# TinyPICO.net
KiCad netlist of a schematic drawn in EAGLE
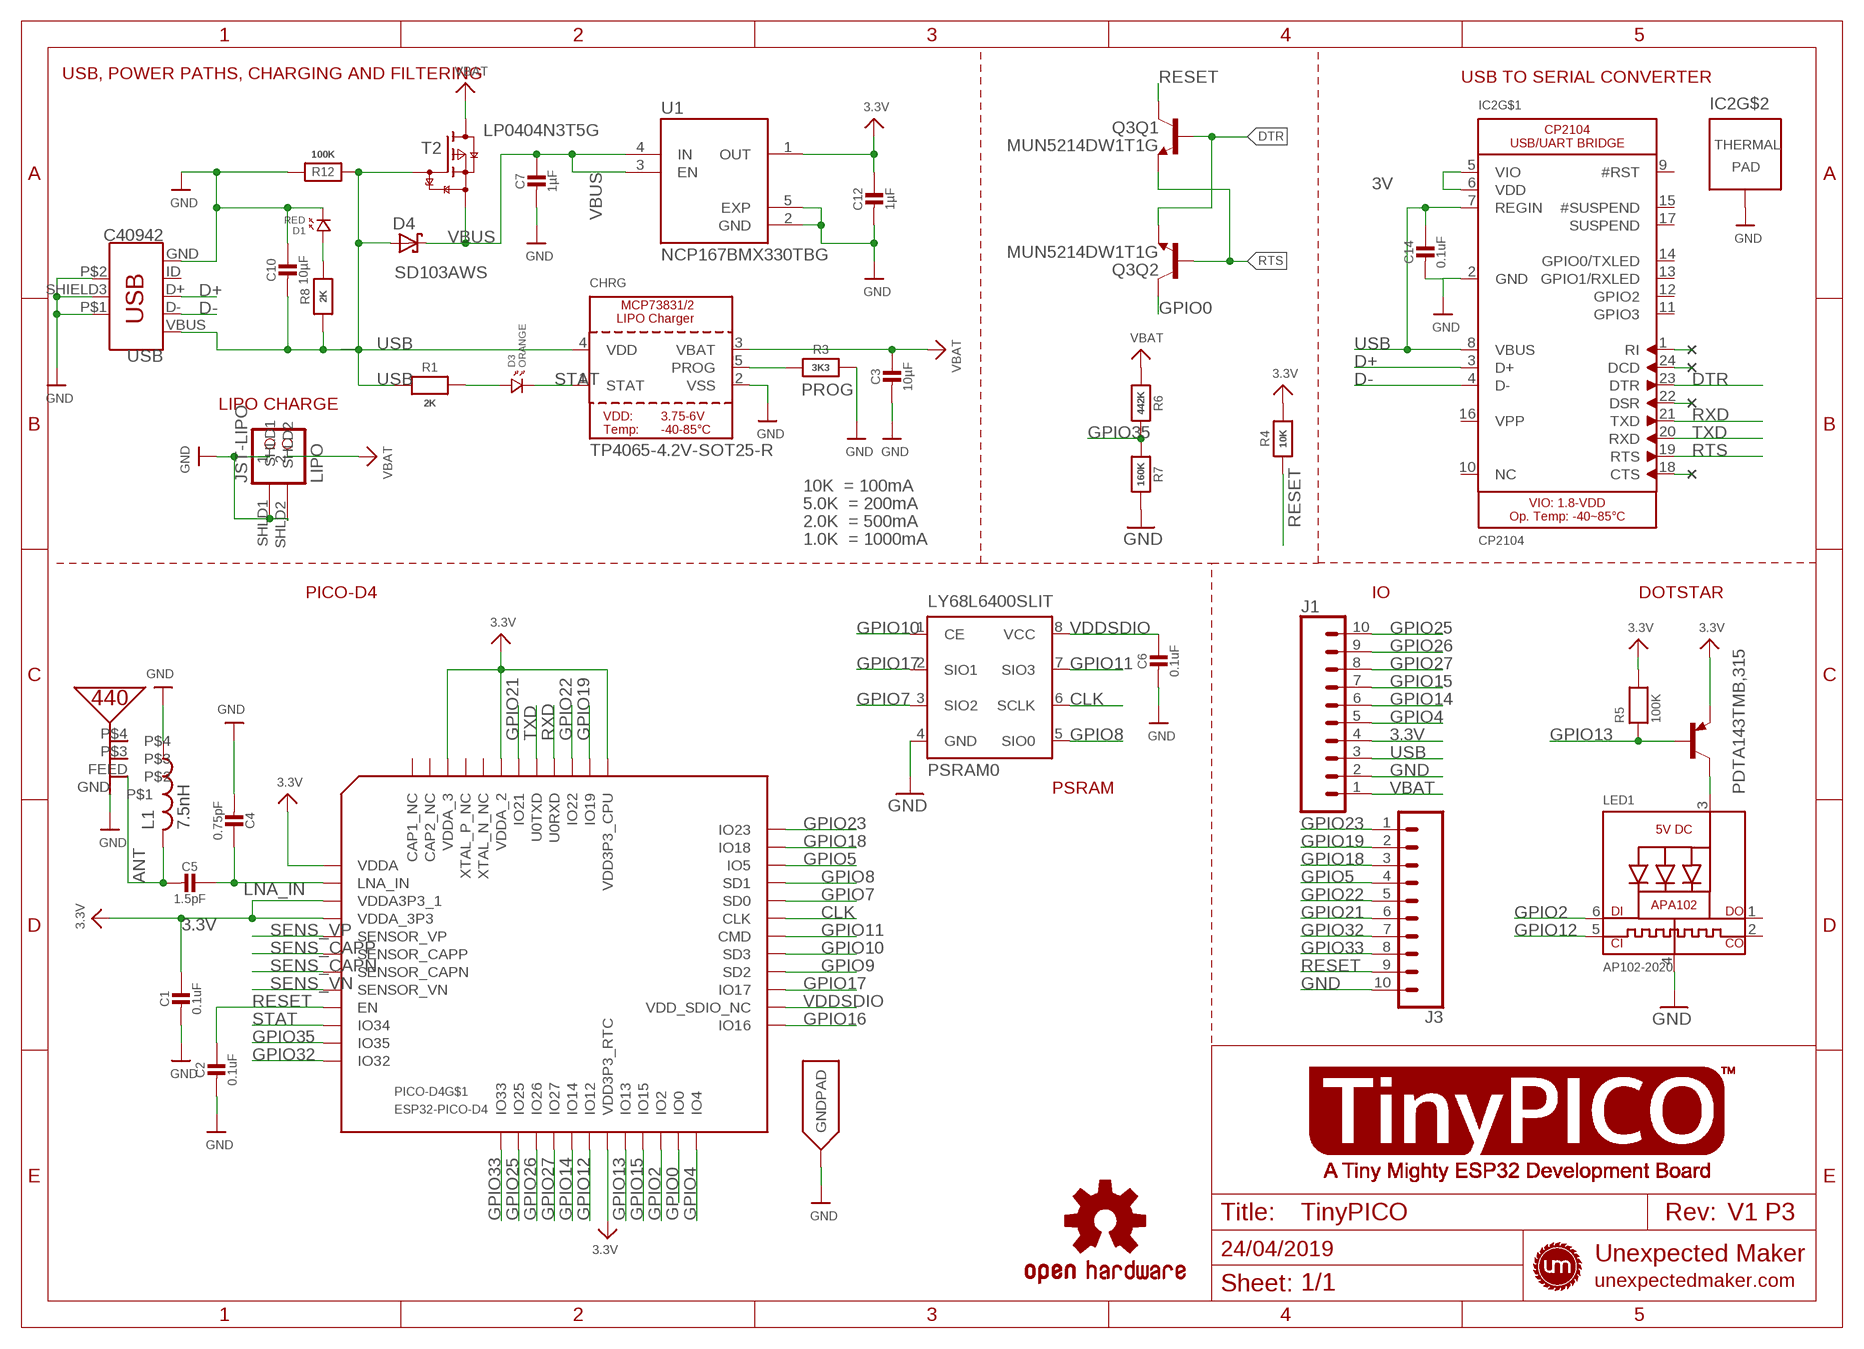
[diagram p0: schematic, sheet 1]

(export (version "E")
  (design (tool "Eeschema 10.0.6"))
  (components
    (comp (ref "C1")
      (value "0.1uF")
      (footprint "eagle-import:_0402MP")
      (libsource (lib "eagle-import") (part "CAP_CERAMIC_0402MP"))
    )
    (comp (ref "C2")
      (value "0.1uF")
      (footprint "eagle-import:_0402MP")
      (libsource (lib "eagle-import") (part "CAP_CERAMIC_0402MP"))
    )
    (comp (ref "C3")
      (value "10µF")
      (footprint "eagle-import:_0603MP")
      (libsource (lib "eagle-import") (part "CAP_CERAMIC_0603MP"))
    )
    (comp (ref "C4")
      (value "0.75pF")
      (footprint "eagle-import:_0402MP")
      (libsource (lib "eagle-import") (part "CAP_CERAMIC_0402MP"))
    )
    (comp (ref "C5")
      (value "1.5pF")
      (footprint "eagle-import:_0402MP")
      (libsource (lib "eagle-import") (part "CAP_CERAMIC_0402MP"))
    )
    (comp (ref "C6")
      (value "0.1uF")
      (footprint "eagle-import:_0402MP")
      (libsource (lib "eagle-import") (part "CAP_CERAMIC_0402MP"))
    )
    (comp (ref "C7")
      (value "1µF")
      (footprint "eagle-import:_0402MP")
      (libsource (lib "eagle-import") (part "CAP_CERAMIC_0402MP"))
    )
    (comp (ref "C10")
      (value "10µF")
      (footprint "eagle-import:_0603MP")
      (libsource (lib "eagle-import") (part "CAP_CERAMIC_0603MP"))
    )
    (comp (ref "C12")
      (value "1µF")
      (footprint "eagle-import:_0402MP")
      (libsource (lib "eagle-import") (part "CAP_CERAMIC_0402MP"))
    )
    (comp (ref "C14")
      (value "0.1uF")
      (footprint "eagle-import:_0402MP")
      (libsource (lib "eagle-import") (part "CAP_CERAMIC_0402MP"))
    )
    (comp (ref "CHRG")
      (value "TP4065-4.2V-SOT25-R")
      (footprint "eagle-import:SOT23-5")
      (libsource (lib "eagle-import") (part "MCP73831/2"))
    )
    (comp (ref "D1")
      (value "RED")
      (footprint "eagle-import:0402.LED")
      (libsource (lib "eagle-import") (part "LED.0402"))
    )
    (comp (ref "D3")
      (value "ORANGE")
      (footprint "eagle-import:0402.LED")
      (libsource (lib "eagle-import") (part "LED.0402"))
    )
    (comp (ref "D4")
      (value "BAT60J")
      (footprint "eagle-import:SOD323_ST")
      (libsource (lib "eagle-import") (part "BAT60J"))
    )
    (comp (ref "IC2")
      (value "CP2104")
      (footprint "eagle-import:MICROBUILDER_QFN24_4MM_SMSC")
      (libsource (lib "eagle-import") (part "MICROBUILDER_CP2104"))
    )
    (comp (ref "J1")
      (value "TINYPICO_HEADER_10NO_SILK_PTH_FEMALE")
      (footprint "eagle-import:1X10_NO_SILK")
      (libsource (lib "eagle-import") (part "TINYPICO_HEADER_10NO_SILK_PTH_FEMALE"))
    )
    (comp (ref "J3")
      (value "TINYPICO_HEADER_10NO_SILK_PTH_FEMALE")
      (footprint "eagle-import:1X10_NO_SILK")
      (libsource (lib "eagle-import") (part "TINYPICO_HEADER_10NO_SILK_PTH_FEMALE"))
    )
    (comp (ref "JST-LIPO")
      (value "LIPO")
      (footprint "eagle-import:JSTPH2")
      (libsource (lib "eagle-import") (part "JST_2PIN"))
    )
    (comp (ref "L1")
      (value "7.5nH")
      (footprint "eagle-import:RESC0402_N")
      (libsource (lib "eagle-import") (part "INDUCTOR_0402_N"))
    )
    (comp (ref "LED1")
      (value "AP102-2020")
      (footprint "eagle-import:MICROBUILDER_APA102_2020")
      (libsource (lib "eagle-import") (part "MICROBUILDER_APA1022020"))
    )
    (comp (ref "LOGO1")
      (value "OSHW-LOGOS")
      (footprint "eagle-import:OSHW-LOGO-S")
      (libsource (lib "eagle-import") (part "OSHW-LOGOS"))
    )
    (comp (ref "LY68L6400SLIT")
      (value "PSRAM0")
      (footprint "eagle-import:SOP8")
      (fields (field (name "MPN") "BD6230F-E2"))
      (libsource (lib "eagle-import") (part "PSRAM0"))
    )
    (comp (ref "PDTA143TMB,315")
      (value "TINYPICO-PNPAMB")
      (footprint "eagle-import:SOT883(B)")
      (libsource (lib "eagle-import") (part "TINYPICO-PNPMBA"))
    )
    (comp (ref "PICO-D4")
      (value "ESP32-PICO-D4")
      (footprint "eagle-import:PICO-D4-QFN48")
      (libsource (lib "eagle-import") (part "ESP32-PICO-D4"))
    )
    (comp (ref "Q3")
      (value "MUN5214DW1T1G")
      (footprint "eagle-import:DUAL_NPN_SC70-6")
      (libsource (lib "eagle-import") (part "MBT3904DW1T1"))
    )
    (comp (ref "R1")
      (value "2K")
      (footprint "eagle-import:_0402MP")
      (libsource (lib "eagle-import") (part "RESISTOR_0402MP"))
    )
    (comp (ref "R3")
      (value "3K3")
      (footprint "eagle-import:_0402MP")
      (libsource (lib "eagle-import") (part "RESISTOR_0402MP"))
    )
    (comp (ref "R4")
      (value "10K")
      (footprint "eagle-import:_0402MP")
      (libsource (lib "eagle-import") (part "RESISTOR_0402MP"))
    )
    (comp (ref "R5")
      (value "100K")
      (footprint "eagle-import:_0402MP")
      (libsource (lib "eagle-import") (part "RESISTOR_0402MP"))
    )
    (comp (ref "R6")
      (value "442K")
      (footprint "eagle-import:_0402MP")
      (libsource (lib "eagle-import") (part "RESISTOR_0402MP"))
    )
    (comp (ref "R7")
      (value "160K")
      (footprint "eagle-import:_0402MP")
      (libsource (lib "eagle-import") (part "RESISTOR_0402MP"))
    )
    (comp (ref "R8")
      (value "2K")
      (footprint "eagle-import:_0402MP")
      (libsource (lib "eagle-import") (part "RESISTOR_0402MP"))
    )
    (comp (ref "R12")
      (value "100K")
      (footprint "eagle-import:_0402MP")
      (libsource (lib "eagle-import") (part "RESISTOR_0402MP"))
    )
    (comp (ref "T2")
      (value "TINYPICO-P-FETKMB")
      (footprint "eagle-import:SOT883(B)")
      (libsource (lib "eagle-import") (part "TINYPICO-P-FETMBK"))
    )
    (comp (ref "U$8")
      (value "PRO-OB-440")
      (footprint "eagle-import:PRO-OB-440")
      (libsource (lib "eagle-import") (part "PRO-OB-440"))
    )
    (comp (ref "U1")
      (value "NCP170AMX300TCG")
      (footprint "eagle-import:VREG_NCP170AMX300TCG")
      (fields (field (name "MF") "ON Semiconductor"))
      (libsource (lib "eagle-import") (part "NCP170AMX300TCG"))
    )
    (comp (ref "USB")
      (value "C40942")
      (footprint "eagle-import:USB-B-MICRO-SMD")
      (libsource (lib "eagle-import") (part "TINYPICO_USB_FEMALE-SMT"))
    )
  )
  (nets
    (net (code "1") (name "/3V") (class "Default")
      (node (ref "IC2") (pin "5") (pinfunction "VIO_5") (pintype "power_in"))
      (node (ref "IC2") (pin "6") (pinfunction "VDD_6") (pintype "power_in"))
    )
    (net (code "2") (name "/ANT") (class "Default")
      (node (ref "C5") (pin "2") (pinfunction "2_2") (pintype "passive"))
      (node (ref "L1") (pin "2") (pinfunction "2_2") (pintype "passive"))
      (node (ref "U$8") (pin "FEED") (pinfunction "P$2_FEED") (pintype "input"))
    )
    (net (code "3") (name "/CLK") (class "Default")
      (node (ref "LY68L6400SLIT") (pin "6") (pinfunction "SCLK_6") (pintype "passive"))
      (node (ref "PICO-D4") (pin "31") (pinfunction "CLK_31") (pintype "bidirectional"))
    )
    (net (code "4") (name "/D+") (class "Default")
      (node (ref "IC2") (pin "3") (pinfunction "D+_3") (pintype "bidirectional"))
      (node (ref "USB") (pin "D+") (pinfunction "D+_D+") (pintype "bidirectional"))
    )
    (net (code "5") (name "/D-") (class "Default")
      (node (ref "IC2") (pin "4") (pinfunction "D-_4") (pintype "bidirectional"))
      (node (ref "USB") (pin "D-") (pinfunction "D-_D-") (pintype "bidirectional"))
    )
    (net (code "6") (name "/GPIO0") (class "Default")
      (node (ref "PICO-D4") (pin "23") (pinfunction "IO0_23") (pintype "bidirectional"))
      (node (ref "Q3") (pin "6") (pinfunction "C_6") (pintype "passive"))
    )
    (net (code "7") (name "/GPIO2") (class "Default")
      (node (ref "LED1") (pin "6") (pinfunction "DI_6") (pintype "input"))
      (node (ref "PICO-D4") (pin "22") (pinfunction "IO2_22") (pintype "bidirectional"))
    )
    (net (code "8") (name "/GPIO4") (class "Default")
      (node (ref "J1") (pin "5") (pinfunction "5_5") (pintype "passive"))
      (node (ref "PICO-D4") (pin "24") (pinfunction "IO4_24") (pintype "bidirectional"))
    )
    (net (code "9") (name "/GPIO5") (class "Default")
      (node (ref "J3") (pin "4") (pinfunction "4_4") (pintype "passive"))
      (node (ref "PICO-D4") (pin "34") (pinfunction "IO5_34") (pintype "bidirectional"))
    )
    (net (code "10") (name "/GPIO7") (class "Default")
      (node (ref "LY68L6400SLIT") (pin "3") (pinfunction "SIO2_3") (pintype "power_in"))
      (node (ref "PICO-D4") (pin "32") (pinfunction "SD0_32") (pintype "bidirectional"))
    )
    (net (code "11") (name "/GPIO8") (class "Default")
      (node (ref "LY68L6400SLIT") (pin "5") (pinfunction "SIO0_5") (pintype "input"))
      (node (ref "PICO-D4") (pin "33") (pinfunction "SD1_33") (pintype "bidirectional"))
    )
    (net (code "12") (name "/GPIO9") (class "Default")
      (node (ref "PICO-D4") (pin "28") (pinfunction "SD2_28") (pintype "bidirectional"))
    )
    (net (code "13") (name "/GPIO10") (class "Default")
      (node (ref "LY68L6400SLIT") (pin "1") (pinfunction "CE_1") (pintype "output"))
      (node (ref "PICO-D4") (pin "29") (pinfunction "SD3_29") (pintype "bidirectional"))
    )
    (net (code "14") (name "/GPIO11") (class "Default")
      (node (ref "LY68L6400SLIT") (pin "7") (pinfunction "SIO3_7") (pintype "output"))
      (node (ref "PICO-D4") (pin "30") (pinfunction "CMD_30") (pintype "bidirectional"))
    )
    (net (code "15") (name "/GPIO12") (class "Default")
      (node (ref "LED1") (pin "5") (pinfunction "CKI_5") (pintype "input"))
      (node (ref "PICO-D4") (pin "18") (pinfunction "IO12_18") (pintype "power_in"))
    )
    (net (code "16") (name "/GPIO13") (class "Default")
      (node (ref "PDTA143TMB,315") (pin "1") (pinfunction "B_1") (pintype "passive"))
      (node (ref "PICO-D4") (pin "20") (pinfunction "IO13_20") (pintype "bidirectional"))
      (node (ref "R5") (pin "1") (pinfunction "1_1") (pintype "passive"))
    )
    (net (code "17") (name "/GPIO14") (class "Default")
      (node (ref "J1") (pin "6") (pinfunction "6_6") (pintype "passive"))
      (node (ref "PICO-D4") (pin "17") (pinfunction "IO14_17") (pintype "bidirectional"))
    )
    (net (code "18") (name "/GPIO15") (class "Default")
      (node (ref "J1") (pin "7") (pinfunction "7_7") (pintype "passive"))
      (node (ref "PICO-D4") (pin "21") (pinfunction "IO15_21") (pintype "bidirectional"))
    )
    (net (code "19") (name "/GPIO16") (class "Default")
      (node (ref "PICO-D4") (pin "25") (pinfunction "IO16_25") (pintype "bidirectional"))
    )
    (net (code "20") (name "/GPIO17") (class "Default")
      (node (ref "LY68L6400SLIT") (pin "2") (pinfunction "SIO1_2") (pintype "power_in"))
      (node (ref "PICO-D4") (pin "27") (pinfunction "IO17_27") (pintype "bidirectional"))
    )
    (net (code "21") (name "/GPIO18") (class "Default")
      (node (ref "J3") (pin "3") (pinfunction "3_3") (pintype "passive"))
      (node (ref "PICO-D4") (pin "35") (pinfunction "IO18_35") (pintype "bidirectional"))
    )
    (net (code "22") (name "/GPIO19") (class "Default")
      (node (ref "J3") (pin "2") (pinfunction "2_2") (pintype "passive"))
      (node (ref "PICO-D4") (pin "38") (pinfunction "IO19_38") (pintype "bidirectional"))
    )
    (net (code "23") (name "/GPIO21") (class "Default")
      (node (ref "J3") (pin "6") (pinfunction "6_6") (pintype "passive"))
      (node (ref "PICO-D4") (pin "42") (pinfunction "IO21_42") (pintype "power_in"))
    )
    (net (code "24") (name "/GPIO22") (class "Default")
      (node (ref "J3") (pin "5") (pinfunction "5_5") (pintype "passive"))
      (node (ref "PICO-D4") (pin "39") (pinfunction "IO22_39") (pintype "bidirectional"))
    )
    (net (code "25") (name "/GPIO23") (class "Default")
      (node (ref "J3") (pin "1") (pinfunction "1_1") (pintype "passive"))
      (node (ref "PICO-D4") (pin "36") (pinfunction "IO23_36") (pintype "bidirectional"))
    )
    (net (code "26") (name "/GPIO25") (class "Default")
      (node (ref "J1") (pin "10") (pinfunction "10_10") (pintype "passive"))
      (node (ref "PICO-D4") (pin "14") (pinfunction "IO25_14") (pintype "bidirectional"))
    )
    (net (code "27") (name "/GPIO26") (class "Default")
      (node (ref "J1") (pin "9") (pinfunction "9_9") (pintype "passive"))
      (node (ref "PICO-D4") (pin "15") (pinfunction "IO26_15") (pintype "bidirectional"))
    )
    (net (code "28") (name "/GPIO27") (class "Default")
      (node (ref "J1") (pin "8") (pinfunction "8_8") (pintype "passive"))
      (node (ref "PICO-D4") (pin "16") (pinfunction "IO27_16") (pintype "bidirectional"))
    )
    (net (code "29") (name "/GPIO32") (class "Default")
      (node (ref "J3") (pin "7") (pinfunction "7_7") (pintype "passive"))
      (node (ref "PICO-D4") (pin "12") (pinfunction "IO32_12") (pintype "bidirectional"))
    )
    (net (code "30") (name "/GPIO33") (class "Default")
      (node (ref "J3") (pin "8") (pinfunction "8_8") (pintype "passive"))
      (node (ref "PICO-D4") (pin "13") (pinfunction "IO33_13") (pintype "bidirectional"))
    )
    (net (code "31") (name "/GPIO35") (class "Default")
      (node (ref "PICO-D4") (pin "11") (pinfunction "IO35_11") (pintype "bidirectional"))
      (node (ref "R6") (pin "2") (pinfunction "2_2") (pintype "passive"))
      (node (ref "R7") (pin "1") (pinfunction "1_1") (pintype "passive"))
    )
    (net (code "32") (name "/LNA_IN") (class "Default")
      (node (ref "C4") (pin "1") (pinfunction "1_1") (pintype "passive"))
      (node (ref "C5") (pin "1") (pinfunction "1_1") (pintype "passive"))
      (node (ref "PICO-D4") (pin "2") (pinfunction "LNA_IN_2") (pintype "bidirectional"))
    )
    (net (code "33") (name "/PROG") (class "Default")
      (node (ref "CHRG") (pin "5") (pinfunction "PROG_5") (pintype "input"))
      (node (ref "R3") (pin "1") (pinfunction "1_1") (pintype "passive"))
    )
    (net (code "34") (name "/RESET") (class "Default")
      (node (ref "C2") (pin "1") (pinfunction "1_1") (pintype "passive"))
      (node (ref "J3") (pin "9") (pinfunction "9_9") (pintype "passive"))
      (node (ref "PICO-D4") (pin "9") (pinfunction "EN_9") (pintype "bidirectional"))
      (node (ref "Q3") (pin "3") (pinfunction "C_3") (pintype "passive"))
      (node (ref "R4") (pin "1") (pinfunction "1_1") (pintype "passive"))
    )
    (net (code "35") (name "/RXD") (class "Default")
      (node (ref "IC2") (pin "21") (pinfunction "TXD_21") (pintype "output"))
      (node (ref "PICO-D4") (pin "40") (pinfunction "U0RXD_40") (pintype "bidirectional"))
    )
    (net (code "36") (name "/SENS_CAPN") (class "Default")
      (node (ref "PICO-D4") (pin "7") (pinfunction "SENSOR_CAPN_7") (pintype "power_in"))
    )
    (net (code "37") (name "/SENS_CAPP") (class "Default")
      (node (ref "PICO-D4") (pin "6") (pinfunction "SENSOR_CAPP_6") (pintype "bidirectional"))
    )
    (net (code "38") (name "/SENS_VN") (class "Default")
      (node (ref "PICO-D4") (pin "8") (pinfunction "SENSOR_VN_8") (pintype "bidirectional"))
    )
    (net (code "39") (name "/SENS_VP") (class "Default")
      (node (ref "PICO-D4") (pin "5") (pinfunction "SENSOR_VP_5") (pintype "bidirectional"))
    )
    (net (code "40") (name "/STAT") (class "Default")
      (node (ref "CHRG") (pin "1") (pinfunction "STAT_1") (pintype "output"))
      (node (ref "D3") (pin "P$2") (pinfunction "2_P$2") (pintype "bidirectional"))
      (node (ref "PICO-D4") (pin "10") (pinfunction "IO34_10") (pintype "bidirectional"))
    )
    (net (code "41") (name "/TXD") (class "Default")
      (node (ref "IC2") (pin "20") (pinfunction "RXD_20") (pintype "input"))
      (node (ref "PICO-D4") (pin "41") (pinfunction "U0TXD_41") (pintype "bidirectional"))
    )
    (net (code "42") (name "/USB") (class "Default")
      (node (ref "C10") (pin "2") (pinfunction "2_2") (pintype "passive"))
      (node (ref "C14") (pin "1") (pinfunction "1_1") (pintype "passive"))
      (node (ref "CHRG") (pin "4") (pinfunction "VDD_4") (pintype "power_in"))
      (node (ref "D4") (pin "A") (pinfunction "A_A") (pintype "passive"))
      (node (ref "IC2") (pin "7") (pinfunction "REGIN_7") (pintype "power_in"))
      (node (ref "IC2") (pin "8") (pinfunction "VBUS_8") (pintype "power_in"))
      (node (ref "J1") (pin "3") (pinfunction "3_3") (pintype "passive"))
      (node (ref "R1") (pin "1") (pinfunction "1_1") (pintype "passive"))
      (node (ref "R12") (pin "1") (pinfunction "1_1") (pintype "passive"))
      (node (ref "R8") (pin "1") (pinfunction "1_1") (pintype "passive"))
      (node (ref "T2") (pin "1") (pinfunction "G_1") (pintype "passive"))
      (node (ref "USB") (pin "VBUS") (pinfunction "VBUS_VBUS") (pintype "power_in"))
    )
    (net (code "43") (name "/VBUS") (class "Default")
      (node (ref "C7") (pin "1") (pinfunction "1_1") (pintype "passive"))
      (node (ref "D4") (pin "C") (pinfunction "C_C") (pintype "passive"))
      (node (ref "T2") (pin "2") (pinfunction "S_2") (pintype "passive"))
      (node (ref "U1") (pin "3") (pinfunction "EN_3") (pintype "input"))
      (node (ref "U1") (pin "4") (pinfunction "IN_4") (pintype "input"))
    )
    (net (code "44") (name "/VDDSDIO") (class "Default")
      (node (ref "C6") (pin "1") (pinfunction "1_1") (pintype "passive"))
      (node (ref "LY68L6400SLIT") (pin "8") (pinfunction "VCC_8") (pintype "power_in"))
      (node (ref "PICO-D4") (pin "26") (pinfunction "VDD_SDIO_NC_26") (pintype "bidirectional"))
    )
    (net (code "45") (name "3.3V") (class "Default")
      (node (ref "C1") (pin "1") (pinfunction "1_1") (pintype "passive"))
      (node (ref "C12") (pin "1") (pinfunction "1_1") (pintype "passive"))
      (node (ref "J1") (pin "4") (pinfunction "4_4") (pintype "passive"))
      (node (ref "PDTA143TMB,315") (pin "2") (pinfunction "E_2") (pintype "passive"))
      (node (ref "PICO-D4") (pin "1") (pinfunction "VDDA_1") (pintype "bidirectional"))
      (node (ref "PICO-D4") (pin "19") (pinfunction "VDD3P3_RTC_19") (pintype "bidirectional"))
      (node (ref "PICO-D4") (pin "3") (pinfunction "VDDA3P3_1_3") (pintype "bidirectional"))
      (node (ref "PICO-D4") (pin "37") (pinfunction "VDD3P3_CPU_37") (pintype "bidirectional"))
      (node (ref "PICO-D4") (pin "4") (pinfunction "VDDA_3P3_4") (pintype "bidirectional"))
      (node (ref "PICO-D4") (pin "43") (pinfunction "VDDA_2_43") (pintype "bidirectional"))
      (node (ref "PICO-D4") (pin "46") (pinfunction "VDDA_3_46") (pintype "bidirectional"))
      (node (ref "R4") (pin "2") (pinfunction "2_2") (pintype "passive"))
      (node (ref "R5") (pin "2") (pinfunction "2_2") (pintype "passive"))
      (node (ref "U1") (pin "1") (pinfunction "OUT_1") (pintype "output"))
    )
    (net (code "46") (name "DTR") (class "Default")
      (node (ref "IC2") (pin "23") (pinfunction "DTR_23") (pintype "output"))
      (node (ref "Q3") (pin "1") (pinfunction "E_1") (pintype "passive"))
      (node (ref "Q3") (pin "5") (pinfunction "B_5") (pintype "passive"))
    )
    (net (code "47") (name "GND") (class "Default")
      (node (ref "C1") (pin "2") (pinfunction "2_2") (pintype "passive"))
      (node (ref "C10") (pin "1") (pinfunction "1_1") (pintype "passive"))
      (node (ref "C12") (pin "2") (pinfunction "2_2") (pintype "passive"))
      (node (ref "C14") (pin "2") (pinfunction "2_2") (pintype "passive"))
      (node (ref "C2") (pin "2") (pinfunction "2_2") (pintype "passive"))
      (node (ref "C3") (pin "2") (pinfunction "2_2") (pintype "passive"))
      (node (ref "C4") (pin "2") (pinfunction "2_2") (pintype "passive"))
      (node (ref "C6") (pin "2") (pinfunction "2_2") (pintype "passive"))
      (node (ref "C7") (pin "2") (pinfunction "2_2") (pintype "passive"))
      (node (ref "CHRG") (pin "2") (pinfunction "VSS_2") (pintype "power_in"))
      (node (ref "D1") (pin "P$2") (pinfunction "2_P$2") (pintype "bidirectional"))
      (node (ref "IC2") (pin "2") (pinfunction "GND_2") (pintype "power_in"))
      (node (ref "IC2") (pin "THERM") (pinfunction "TP_THERM") (pintype "power_in"))
      (node (ref "J1") (pin "2") (pinfunction "2_2") (pintype "passive"))
      (node (ref "J3") (pin "10") (pinfunction "10_10") (pintype "passive"))
      (node (ref "JST-LIPO") (pin "1") (pinfunction "1_1") (pintype "passive"))
      (node (ref "JST-LIPO") (pin "SHLD1") (pinfunction "SHLD1_SHLD1") (pintype "bidirectional"))
      (node (ref "JST-LIPO") (pin "SHLD2") (pinfunction "SHLD2_SHLD2") (pintype "bidirectional"))
      (node (ref "L1") (pin "1") (pinfunction "1_1") (pintype "passive"))
      (node (ref "LED1") (pin "4") (pinfunction "GND_4") (pintype "power_in"))
      (node (ref "LY68L6400SLIT") (pin "4") (pinfunction "GND_4") (pintype "input"))
      (node (ref "PICO-D4") (pin "EXP") (pinfunction "GNDPAD_EXP") (pintype "power_in"))
      (node (ref "R12") (pin "2") (pinfunction "2_2") (pintype "passive"))
      (node (ref "R3") (pin "2") (pinfunction "2_2") (pintype "passive"))
      (node (ref "R7") (pin "2") (pinfunction "2_2") (pintype "passive"))
      (node (ref "U$8") (pin "GND") (pinfunction "P$1_GND") (pintype "input"))
      (node (ref "U1") (pin "2") (pinfunction "GND_2") (pintype "power_in"))
      (node (ref "U1") (pin "5") (pinfunction "EXP_5") (pintype "power_in"))
      (node (ref "USB") (pin "GND") (pinfunction "GND_GND") (pintype "power_in"))
      (node (ref "USB") (pin "P$1") (pinfunction "SHIELD1_P$1") (pintype "bidirectional"))
      (node (ref "USB") (pin "P$2") (pinfunction "SHIELD2_P$2") (pintype "bidirectional"))
      (node (ref "USB") (pin "SHIELD3") (pinfunction "SHIELD_SHIELD3") (pintype "bidirectional"))
    )
    (net (code "48") (name "Net-(D1-1)") (class "Default")
      (node (ref "D1") (pin "P$1") (pinfunction "1_P$1") (pintype "bidirectional"))
      (node (ref "R8") (pin "2") (pinfunction "2_2") (pintype "passive"))
    )
    (net (code "49") (name "Net-(D3-1)") (class "Default")
      (node (ref "D3") (pin "P$1") (pinfunction "1_P$1") (pintype "bidirectional"))
      (node (ref "R1") (pin "2") (pinfunction "2_2") (pintype "passive"))
    )
    (net (code "50") (name "Net-(LED1-VDD)") (class "Default")
      (node (ref "LED1") (pin "3") (pinfunction "VDD_3") (pintype "power_in"))
      (node (ref "PDTA143TMB,315") (pin "3") (pinfunction "C_3") (pintype "passive"))
    )
    (net (code "51") (name "RTS") (class "Default")
      (node (ref "IC2") (pin "19") (pinfunction "RTS_19") (pintype "output"))
      (node (ref "Q3") (pin "2") (pinfunction "B_2") (pintype "passive"))
      (node (ref "Q3") (pin "4") (pinfunction "E_4") (pintype "passive"))
    )
    (net (code "52") (name "VBAT") (class "Default")
      (node (ref "C3") (pin "1") (pinfunction "1_1") (pintype "passive"))
      (node (ref "CHRG") (pin "3") (pinfunction "VBAT_3") (pintype "power_in"))
      (node (ref "J1") (pin "1") (pinfunction "1_1") (pintype "passive"))
      (node (ref "JST-LIPO") (pin "2") (pinfunction "2_2") (pintype "passive"))
      (node (ref "R6") (pin "1") (pinfunction "1_1") (pintype "passive"))
      (node (ref "T2") (pin "3") (pinfunction "D_3") (pintype "passive"))
    )
    (net (code "53") (name "unconnected-(IC2A-#RST-Pad9)") (class "Default")
      (node (ref "IC2") (pin "9") (pinfunction "#RST_9") (pintype "bidirectional"))
    )
    (net (code "54") (name "unconnected-(IC2A-#SUSPEND-Pad15)") (class "Default")
      (node (ref "IC2") (pin "15") (pinfunction "#SUSPEND_15") (pintype "output"))
    )
    (net (code "55") (name "unconnected-(IC2A-CTS-Pad18)") (class "Default")
      (node (ref "IC2") (pin "18") (pinfunction "CTS_18") (pintype "input"))
    )
    (net (code "56") (name "unconnected-(IC2A-DCD-Pad24)") (class "Default")
      (node (ref "IC2") (pin "24") (pinfunction "DCD_24") (pintype "input"))
    )
    (net (code "57") (name "unconnected-(IC2A-DSR-Pad22)") (class "Default")
      (node (ref "IC2") (pin "22") (pinfunction "DSR_22") (pintype "input"))
    )
    (net (code "58") (name "unconnected-(IC2A-GPIO0{slash}TXLED-Pad14)") (class "Default")
      (node (ref "IC2") (pin "14") (pinfunction "GPIO0/TXLED_14") (pintype "bidirectional"))
    )
    (net (code "59") (name "unconnected-(IC2A-GPIO1{slash}RXLED-Pad13)") (class "Default")
      (node (ref "IC2") (pin "13") (pinfunction "GPIO1/RXLED_13") (pintype "bidirectional"))
    )
    (net (code "60") (name "unconnected-(IC2A-GPIO2-Pad12)") (class "Default")
      (node (ref "IC2") (pin "12") (pinfunction "GPIO2_12") (pintype "bidirectional"))
    )
    (net (code "61") (name "unconnected-(IC2A-GPIO3-Pad11)") (class "Default")
      (node (ref "IC2") (pin "11") (pinfunction "GPIO3_11") (pintype "bidirectional"))
    )
    (net (code "62") (name "unconnected-(IC2A-NC-Pad10)") (class "Default")
      (node (ref "IC2") (pin "10") (pinfunction "NC_10") (pintype "no_connect"))
    )
    (net (code "63") (name "unconnected-(IC2A-RI-Pad1)") (class "Default")
      (node (ref "IC2") (pin "1") (pinfunction "RI_1") (pintype "input"))
    )
    (net (code "64") (name "unconnected-(IC2A-SUSPEND-Pad17)") (class "Default")
      (node (ref "IC2") (pin "17") (pinfunction "SUSPEND_17") (pintype "output"))
    )
    (net (code "65") (name "unconnected-(IC2A-VPP-Pad16)") (class "Default")
      (node (ref "IC2") (pin "16") (pinfunction "VPP_16") (pintype "bidirectional"))
    )
    (net (code "66") (name "unconnected-(LED1-CKO-Pad2)") (class "Default")
      (node (ref "LED1") (pin "2") (pinfunction "CKO_2") (pintype "output"))
    )
    (net (code "67") (name "unconnected-(LED1-DO-Pad1)") (class "Default")
      (node (ref "LED1") (pin "1") (pinfunction "DO_1") (pintype "output"))
    )
    (net (code "68") (name "unconnected-(PICO-D4A-CAP1_NC-Pad48)") (class "Default")
      (node (ref "PICO-D4") (pin "48") (pinfunction "CAP1_NC_48") (pintype "bidirectional"))
    )
    (net (code "69") (name "unconnected-(PICO-D4A-CAP2_NC-Pad47)") (class "Default")
      (node (ref "PICO-D4") (pin "47") (pinfunction "CAP2_NC_47") (pintype "bidirectional"))
    )
    (net (code "70") (name "unconnected-(PICO-D4A-XTAL_N_NC-Pad44)") (class "Default")
      (node (ref "PICO-D4") (pin "44") (pinfunction "XTAL_N_NC_44") (pintype "bidirectional"))
    )
    (net (code "71") (name "unconnected-(PICO-D4A-XTAL_P_NC-Pad45)") (class "Default")
      (node (ref "PICO-D4") (pin "45") (pinfunction "XTAL_P_NC_45") (pintype "bidirectional"))
    )
    (net (code "72") (name "unconnected-(U$8-PadP$3)") (class "Default")
      (node (ref "U$8") (pin "P$3") (pinfunction "P$3_P$3") (pintype "no_connect"))
    )
    (net (code "73") (name "unconnected-(U$8-PadP$4)") (class "Default")
      (node (ref "U$8") (pin "P$4") (pinfunction "P$4_P$4") (pintype "no_connect"))
    )
    (net (code "74") (name "unconnected-(USB-PadID)") (class "Default")
      (node (ref "USB") (pin "ID") (pinfunction "ID_ID") (pintype "bidirectional"))
    )
  )
)
